# programador_ATtiny_easyeda.net
KiCad netlist of a schematic drawn in EasyEDA
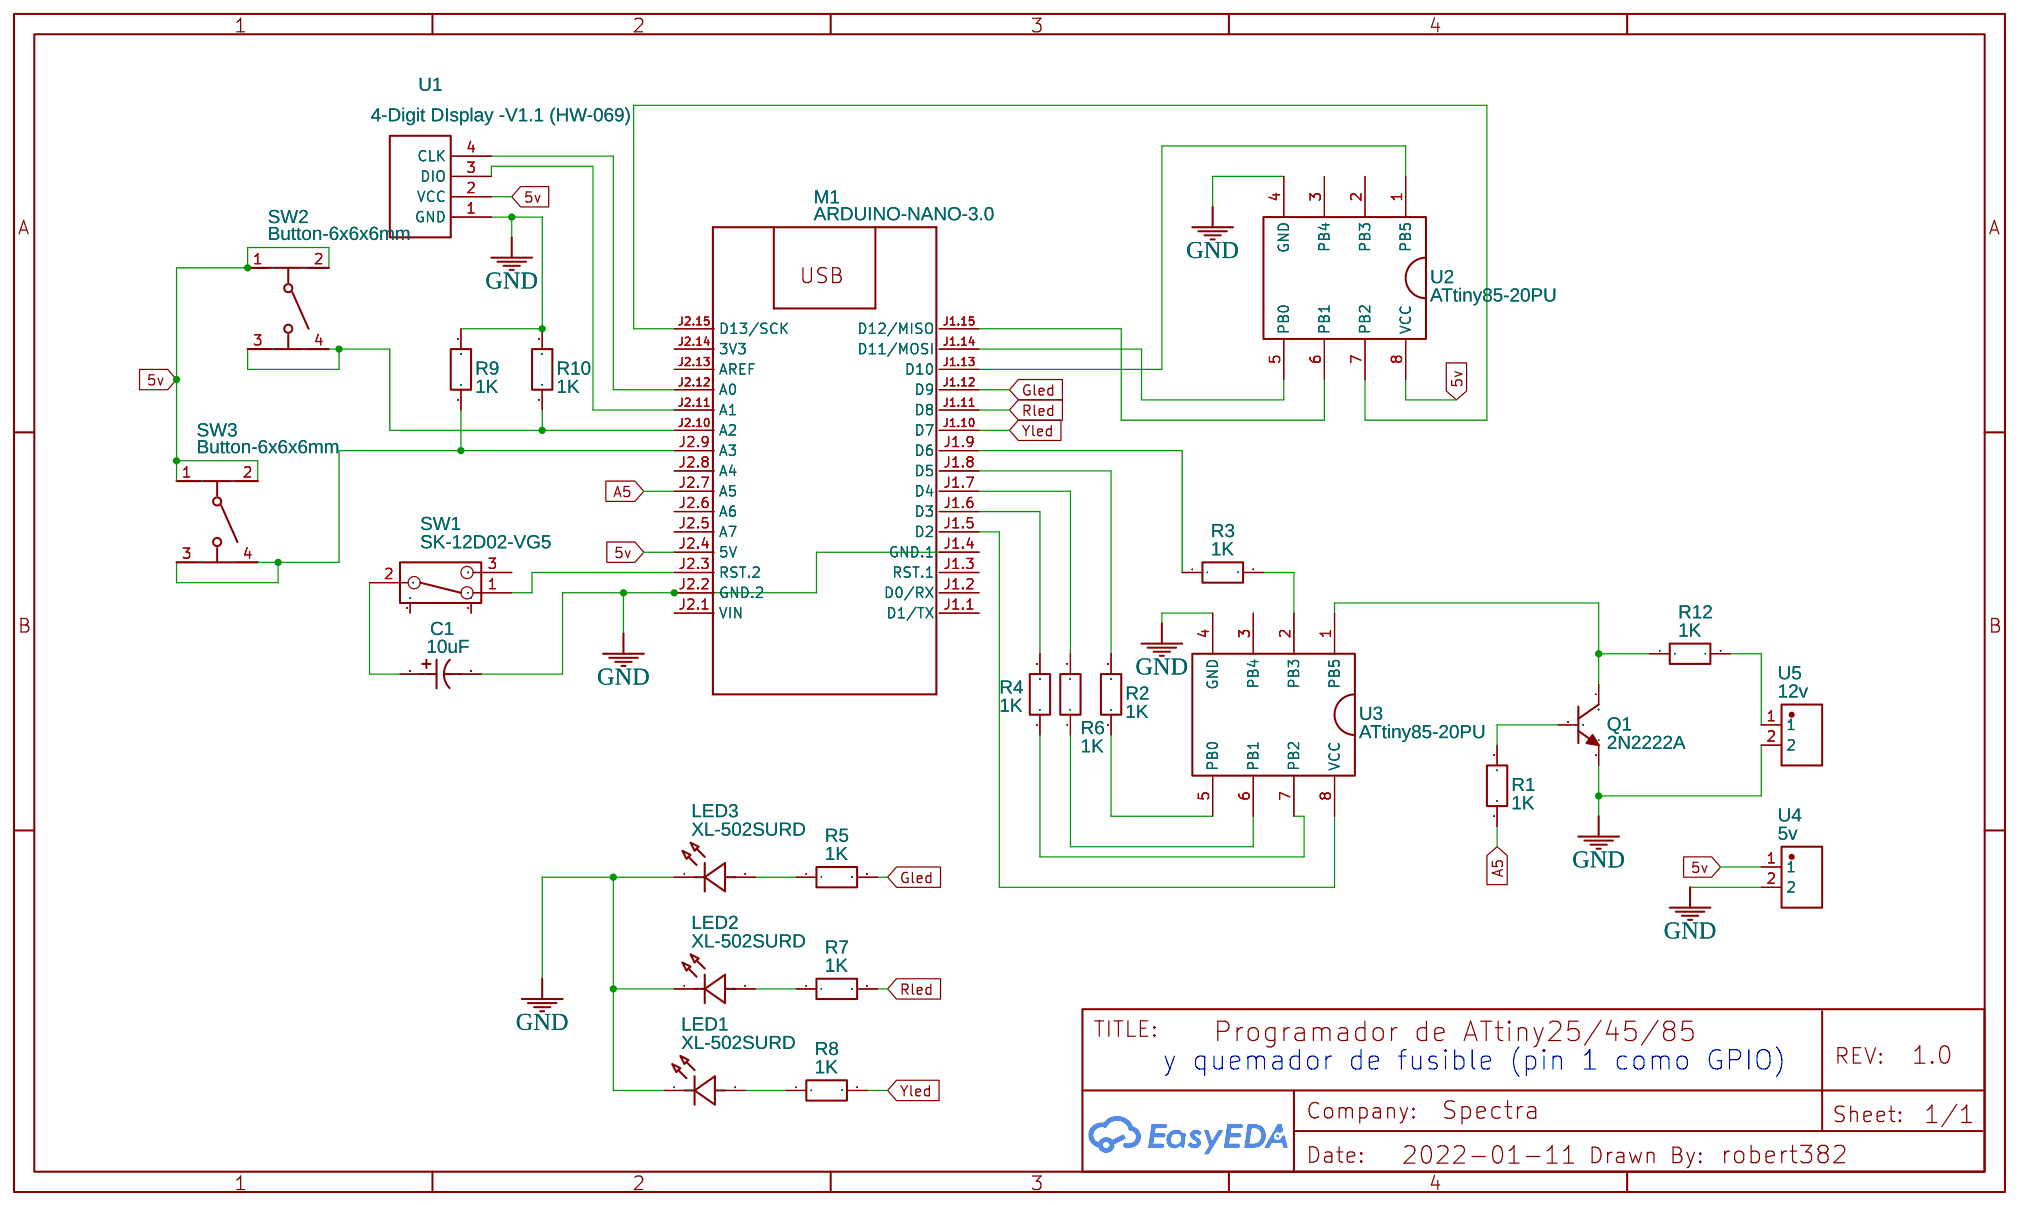
[diagram p0: schematic sheet]

(export (version "E")
  (design (tool "Eeschema 10.0.6"))
  (components
    (comp (ref "C1")
      (value "10uF")
      (fields
        (field (name "BOM_Manufacturer Part") "RA3-50V100ME3#")
        (field (name "BOM_Supplier Part") "C399591")
      )
      (libsource (lib "") (part "RA3-50V100ME3#"))
    )
    (comp (ref "LED1")
      (value "XL-502SURD")
      (fields (field (name "BOM_Supplier Part") "C2895492"))
      (libsource (lib "") (part "XL-502SURD"))
    )
    (comp (ref "LED2")
      (value "XL-502SURD")
      (fields (field (name "BOM_Supplier Part") "C2895492"))
      (libsource (lib "") (part "XL-502SURD"))
    )
    (comp (ref "LED3")
      (value "XL-502SURD")
      (fields (field (name "BOM_Supplier Part") "C2895492"))
      (libsource (lib "") (part "XL-502SURD"))
    )
    (comp (ref "M1") (value "ARDUINO-NANO-3.0") (libsource (lib "") (part "ARDUINO-NANO-3.0")))
    (comp (ref "Q1")
      (value "2N2222A")
      (fields (field (name "BOM_Supplier Part") "C358533"))
      (libsource (lib "") (part "2N2222A"))
    )
    (comp (ref "R1")
      (value "1K")
      (fields
        (field (name "BOM_Manufacturer Part") "MFR0W8F1001A50")
        (field (name "BOM_Supplier Part") "C61238")
      )
      (libsource (lib "") (part "MFR0W8F1001A50_C61238_1"))
    )
    (comp (ref "R2")
      (value "1K")
      (fields
        (field (name "BOM_Manufacturer Part") "MFR0W8F1001A50")
        (field (name "BOM_Supplier Part") "C61238")
      )
      (libsource (lib "") (part "MFR0W8F1001A50_C61238_1"))
    )
    (comp (ref "R3")
      (value "1K")
      (fields
        (field (name "BOM_Manufacturer Part") "MFR0W8F1001A50")
        (field (name "BOM_Supplier Part") "C61238")
      )
      (libsource (lib "") (part "MFR0W8F1001A50_C61238"))
    )
    (comp (ref "R4")
      (value "1K")
      (fields
        (field (name "BOM_Manufacturer Part") "MFR0W8F1001A50")
        (field (name "BOM_Supplier Part") "C61238")
      )
      (libsource (lib "") (part "MFR0W8F1001A50_C61238_1"))
    )
    (comp (ref "R5")
      (value "1K")
      (fields
        (field (name "BOM_Manufacturer Part") "MFR0W8F1001A50")
        (field (name "BOM_Supplier Part") "C61238")
      )
      (libsource (lib "") (part "MFR0W8F1001A50_C61238"))
    )
    (comp (ref "R6")
      (value "1K")
      (fields
        (field (name "BOM_Manufacturer Part") "MFR0W8F1001A50")
        (field (name "BOM_Supplier Part") "C61238")
      )
      (libsource (lib "") (part "MFR0W8F1001A50_C61238_1"))
    )
    (comp (ref "R7")
      (value "1K")
      (fields
        (field (name "BOM_Manufacturer Part") "MFR0W8F1001A50")
        (field (name "BOM_Supplier Part") "C61238")
      )
      (libsource (lib "") (part "MFR0W8F1001A50_C61238"))
    )
    (comp (ref "R8")
      (value "1K")
      (fields
        (field (name "BOM_Manufacturer Part") "MFR0W8F1001A50")
        (field (name "BOM_Supplier Part") "C61238")
      )
      (libsource (lib "") (part "MFR0W8F1001A50_C61238"))
    )
    (comp (ref "R9")
      (value "1K")
      (fields
        (field (name "BOM_Manufacturer Part") "MFR0W8F1001A50")
        (field (name "BOM_Supplier Part") "C61238")
      )
      (libsource (lib "") (part "MFR0W8F1001A50_C61238_1"))
    )
    (comp (ref "R10")
      (value "1K")
      (fields
        (field (name "BOM_Manufacturer Part") "MFR0W8F1001A50")
        (field (name "BOM_Supplier Part") "C61238")
      )
      (libsource (lib "") (part "MFR0W8F1001A50_C61238_1"))
    )
    (comp (ref "R12")
      (value "1K")
      (fields
        (field (name "BOM_Manufacturer Part") "MFR0W8F1001A50")
        (field (name "BOM_Supplier Part") "C61238")
      )
      (libsource (lib "") (part "MFR0W8F1001A50_C61238"))
    )
    (comp (ref "SW1")
      (value "SK-12D02-VG5")
      (fields (field (name "BOM_Supplier Part") "C136722"))
      (libsource (lib "") (part "SK-12D02-VG5"))
    )
    (comp (ref "SW2")
      (value "Button-6x6x6mm")
      (fields
        (field (name "BOM_Manufacturer Part") "Switch,6*6*6Plastic head,260G, 0.25mm,Straight line")
        (field (name "BOM_Supplier Part") "C71836")
      )
      (libsource (lib "") (part "Button-6x6x6mm"))
    )
    (comp (ref "SW3")
      (value "Button-6x6x6mm")
      (fields
        (field (name "BOM_Manufacturer Part") "Switch,6*6*6Plastic head,260G, 0.25mm,Straight line")
        (field (name "BOM_Supplier Part") "C71836")
      )
      (libsource (lib "") (part "Button-6x6x6mm"))
    )
    (comp (ref "U1")
      (value "4-Digit DIsplay -V1.1 (HW-069)")
      (libsource (lib "") (part "4-Digit DIsplay -V1.1 (HW-069)"))
    )
    (comp (ref "U2")
      (value "ATtiny85-20PU")
      (fields
        (field (name "BOM_Manufacturer Part") "ATTINY85-20PU")
        (field (name "BOM_Supplier Part") "556-ATTINY85-20PU")
      )
      (libsource (lib "") (part "ATtiny85-20PU"))
    )
    (comp (ref "U3")
      (value "ATtiny85-20PU")
      (fields
        (field (name "BOM_Manufacturer Part") "ATTINY85-20PU")
        (field (name "BOM_Supplier Part") "556-ATTINY85-20PU")
      )
      (libsource (lib "") (part "ATtiny85-20PU"))
    )
    (comp (ref "U4")
      (value "5v")
      (fields
        (field (name "BOM_Manufacturer Part") "KY0200500000G")
        (field (name "BOM_Supplier Part") "C967069")
      )
      (libsource (lib "") (part "KY0200500000G"))
    )
    (comp (ref "U5")
      (value "12v")
      (fields
        (field (name "BOM_Manufacturer Part") "KY0200500000G")
        (field (name "BOM_Supplier Part") "C967069")
      )
      (libsource (lib "") (part "KY0200500000G"))
    )
  )
  (nets
    (net (code "1") (name "5v") (class "Default")
      (node (ref "M1") (pin "J2.4") (pinfunction "5V_J2.4") (pintype "bidirectional"))
      (node (ref "SW2") (pin "1") (pinfunction "1_1") (pintype "unspecified"))
      (node (ref "SW2") (pin "2") (pinfunction "2_2") (pintype "unspecified"))
      (node (ref "SW3") (pin "1") (pinfunction "1_1") (pintype "unspecified"))
      (node (ref "SW3") (pin "2") (pinfunction "2_2") (pintype "unspecified"))
      (node (ref "U1") (pin "2") (pinfunction "VCC_2") (pintype "unspecified"))
      (node (ref "U2") (pin "8") (pinfunction "VCC_8") (pintype "unspecified"))
      (node (ref "U4") (pin "1") (pinfunction "1_1") (pintype "unspecified"))
    )
    (net (code "2") (name "A5") (class "Default")
      (node (ref "M1") (pin "J2.7") (pinfunction "A5_J2.7") (pintype "bidirectional"))
      (node (ref "R1") (pin "1") (pinfunction "1_1") (pintype "unspecified"))
    )
    (net (code "3") (name "GND") (class "Default")
      (node (ref "C1") (pin "2") (pinfunction "2_2") (pintype "input"))
      (node (ref "LED1") (pin "1") (pinfunction "K_1") (pintype "unspecified"))
      (node (ref "LED2") (pin "1") (pinfunction "K_1") (pintype "unspecified"))
      (node (ref "LED3") (pin "1") (pinfunction "K_1") (pintype "unspecified"))
      (node (ref "M1") (pin "J1.4") (pinfunction "GND.1_J1.4") (pintype "bidirectional"))
      (node (ref "M1") (pin "J2.2") (pinfunction "GND.2_J2.2") (pintype "bidirectional"))
      (node (ref "Q1") (pin "3") (pinfunction "E_3") (pintype "unspecified"))
      (node (ref "R10") (pin "2") (pinfunction "2_2") (pintype "unspecified"))
      (node (ref "R9") (pin "2") (pinfunction "2_2") (pintype "unspecified"))
      (node (ref "U1") (pin "1") (pinfunction "GND_1") (pintype "unspecified"))
      (node (ref "U2") (pin "4") (pinfunction "GND_4") (pintype "unspecified"))
      (node (ref "U3") (pin "4") (pinfunction "GND_4") (pintype "unspecified"))
      (node (ref "U4") (pin "2") (pinfunction "2_2") (pintype "unspecified"))
      (node (ref "U5") (pin "2") (pinfunction "2_2") (pintype "unspecified"))
    )
    (net (code "4") (name "Gled") (class "Default")
      (node (ref "M1") (pin "J1.12") (pinfunction "D9_J1.12") (pintype "bidirectional"))
      (node (ref "R5") (pin "2") (pinfunction "2_2") (pintype "unspecified"))
    )
    (net (code "5") (name "Net-(C1-Pad1)") (class "Default")
      (node (ref "C1") (pin "1") (pinfunction "1_1") (pintype "input"))
      (node (ref "SW1") (pin "2") (pinfunction "2_2") (pintype "unspecified"))
    )
    (net (code "6") (name "Net-(LED1-A)") (class "Default")
      (node (ref "LED1") (pin "2") (pinfunction "A_2") (pintype "unspecified"))
      (node (ref "R8") (pin "1") (pinfunction "1_1") (pintype "unspecified"))
    )
    (net (code "7") (name "Net-(LED2-A)") (class "Default")
      (node (ref "LED2") (pin "2") (pinfunction "A_2") (pintype "unspecified"))
      (node (ref "R7") (pin "1") (pinfunction "1_1") (pintype "unspecified"))
    )
    (net (code "8") (name "Net-(LED3-A)") (class "Default")
      (node (ref "LED3") (pin "2") (pinfunction "A_2") (pintype "unspecified"))
      (node (ref "R5") (pin "1") (pinfunction "1_1") (pintype "unspecified"))
    )
    (net (code "9") (name "Net-(M1-A0)") (class "Default")
      (node (ref "M1") (pin "J2.12") (pinfunction "A0_J2.12") (pintype "bidirectional"))
      (node (ref "U1") (pin "4") (pinfunction "CLK_4") (pintype "unspecified"))
    )
    (net (code "10") (name "Net-(M1-A1)") (class "Default")
      (node (ref "M1") (pin "J2.11") (pinfunction "A1_J2.11") (pintype "bidirectional"))
      (node (ref "U1") (pin "3") (pinfunction "DIO_3") (pintype "unspecified"))
    )
    (net (code "11") (name "Net-(M1-A2)") (class "Default")
      (node (ref "M1") (pin "J2.10") (pinfunction "A2_J2.10") (pintype "bidirectional"))
      (node (ref "R10") (pin "1") (pinfunction "1_1") (pintype "unspecified"))
      (node (ref "SW2") (pin "3") (pinfunction "3_3") (pintype "unspecified"))
      (node (ref "SW2") (pin "4") (pinfunction "4_4") (pintype "unspecified"))
    )
    (net (code "12") (name "Net-(M1-A3)") (class "Default")
      (node (ref "M1") (pin "J2.9") (pinfunction "A3_J2.9") (pintype "bidirectional"))
      (node (ref "R9") (pin "1") (pinfunction "1_1") (pintype "unspecified"))
      (node (ref "SW3") (pin "3") (pinfunction "3_3") (pintype "unspecified"))
      (node (ref "SW3") (pin "4") (pinfunction "4_4") (pintype "unspecified"))
    )
    (net (code "13") (name "Net-(M1-D2)") (class "Default")
      (node (ref "M1") (pin "J1.5") (pinfunction "D2_J1.5") (pintype "bidirectional"))
      (node (ref "U3") (pin "8") (pinfunction "VCC_8") (pintype "unspecified"))
    )
    (net (code "14") (name "Net-(M1-D3)") (class "Default")
      (node (ref "M1") (pin "J1.6") (pinfunction "D3_J1.6") (pintype "bidirectional"))
      (node (ref "R4") (pin "2") (pinfunction "2_2") (pintype "unspecified"))
    )
    (net (code "15") (name "Net-(M1-D4)") (class "Default")
      (node (ref "M1") (pin "J1.7") (pinfunction "D4_J1.7") (pintype "bidirectional"))
      (node (ref "R6") (pin "2") (pinfunction "2_2") (pintype "unspecified"))
    )
    (net (code "16") (name "Net-(M1-D5)") (class "Default")
      (node (ref "M1") (pin "J1.8") (pinfunction "D5_J1.8") (pintype "bidirectional"))
      (node (ref "R2") (pin "2") (pinfunction "2_2") (pintype "unspecified"))
    )
    (net (code "17") (name "Net-(M1-D6)") (class "Default")
      (node (ref "M1") (pin "J1.9") (pinfunction "D6_J1.9") (pintype "bidirectional"))
      (node (ref "R3") (pin "1") (pinfunction "1_1") (pintype "unspecified"))
    )
    (net (code "18") (name "Net-(M1-D10)") (class "Default")
      (node (ref "M1") (pin "J1.13") (pinfunction "D10_J1.13") (pintype "bidirectional"))
      (node (ref "U2") (pin "1") (pinfunction "PB5_1") (pintype "unspecified"))
    )
    (net (code "19") (name "Net-(M1-D11{slash}MOSI)") (class "Default")
      (node (ref "M1") (pin "J1.14") (pinfunction "D11/MOSI_J1.14") (pintype "bidirectional"))
      (node (ref "U2") (pin "5") (pinfunction "PB0_5") (pintype "unspecified"))
    )
    (net (code "20") (name "Net-(M1-D12{slash}MISO)") (class "Default")
      (node (ref "M1") (pin "J1.15") (pinfunction "D12/MISO_J1.15") (pintype "bidirectional"))
      (node (ref "U2") (pin "6") (pinfunction "PB1_6") (pintype "unspecified"))
    )
    (net (code "21") (name "Net-(M1-D13{slash}SCK)") (class "Default")
      (node (ref "M1") (pin "J2.15") (pinfunction "D13/SCK_J2.15") (pintype "bidirectional"))
      (node (ref "U2") (pin "7") (pinfunction "PB2_7") (pintype "unspecified"))
    )
    (net (code "22") (name "Net-(M1-RST.2)") (class "Default")
      (node (ref "M1") (pin "J2.3") (pinfunction "RST.2_J2.3") (pintype "bidirectional"))
      (node (ref "SW1") (pin "1") (pinfunction "1_1") (pintype "unspecified"))
    )
    (net (code "23") (name "Net-(Q1-B)") (class "Default")
      (node (ref "Q1") (pin "2") (pinfunction "B_2") (pintype "unspecified"))
      (node (ref "R1") (pin "2") (pinfunction "2_2") (pintype "unspecified"))
    )
    (net (code "24") (name "Net-(Q1-C)") (class "Default")
      (node (ref "Q1") (pin "1") (pinfunction "C_1") (pintype "unspecified"))
      (node (ref "R12") (pin "1") (pinfunction "1_1") (pintype "unspecified"))
      (node (ref "U3") (pin "1") (pinfunction "PB5_1") (pintype "unspecified"))
    )
    (net (code "25") (name "Net-(R12-Pad2)") (class "Default")
      (node (ref "R12") (pin "2") (pinfunction "2_2") (pintype "unspecified"))
      (node (ref "U5") (pin "1") (pinfunction "1_1") (pintype "unspecified"))
    )
    (net (code "26") (name "Net-(U3-PB0)") (class "Default")
      (node (ref "R2") (pin "1") (pinfunction "1_1") (pintype "unspecified"))
      (node (ref "U3") (pin "5") (pinfunction "PB0_5") (pintype "unspecified"))
    )
    (net (code "27") (name "Net-(U3-PB1)") (class "Default")
      (node (ref "R6") (pin "1") (pinfunction "1_1") (pintype "unspecified"))
      (node (ref "U3") (pin "6") (pinfunction "PB1_6") (pintype "unspecified"))
    )
    (net (code "28") (name "Net-(U3-PB2)") (class "Default")
      (node (ref "R4") (pin "1") (pinfunction "1_1") (pintype "unspecified"))
      (node (ref "U3") (pin "7") (pinfunction "PB2_7") (pintype "unspecified"))
    )
    (net (code "29") (name "Net-(U3-PB3)") (class "Default")
      (node (ref "R3") (pin "2") (pinfunction "2_2") (pintype "unspecified"))
      (node (ref "U3") (pin "2") (pinfunction "PB3_2") (pintype "unspecified"))
    )
    (net (code "30") (name "Rled") (class "Default")
      (node (ref "M1") (pin "J1.11") (pinfunction "D8_J1.11") (pintype "bidirectional"))
      (node (ref "R7") (pin "2") (pinfunction "2_2") (pintype "unspecified"))
    )
    (net (code "31") (name "Yled") (class "Default")
      (node (ref "M1") (pin "J1.10") (pinfunction "D7_J1.10") (pintype "bidirectional"))
      (node (ref "R8") (pin "2") (pinfunction "2_2") (pintype "unspecified"))
    )
    (net (code "32") (name "unconnected-(M1-3V3-PadJ2.14)") (class "Default")
      (node (ref "M1") (pin "J2.14") (pinfunction "3V3_J2.14") (pintype "bidirectional"))
    )
    (net (code "33") (name "unconnected-(M1-A4-PadJ2.8)") (class "Default")
      (node (ref "M1") (pin "J2.8") (pinfunction "A4_J2.8") (pintype "bidirectional"))
    )
    (net (code "34") (name "unconnected-(M1-A6-PadJ2.6)") (class "Default")
      (node (ref "M1") (pin "J2.6") (pinfunction "A6_J2.6") (pintype "bidirectional"))
    )
    (net (code "35") (name "unconnected-(M1-A7-PadJ2.5)") (class "Default")
      (node (ref "M1") (pin "J2.5") (pinfunction "A7_J2.5") (pintype "bidirectional"))
    )
    (net (code "36") (name "unconnected-(M1-AREF-PadJ2.13)") (class "Default")
      (node (ref "M1") (pin "J2.13") (pinfunction "AREF_J2.13") (pintype "bidirectional"))
    )
    (net (code "37") (name "unconnected-(M1-D0{slash}RX-PadJ1.2)") (class "Default")
      (node (ref "M1") (pin "J1.2") (pinfunction "D0/RX_J1.2") (pintype "bidirectional"))
    )
    (net (code "38") (name "unconnected-(M1-D1{slash}TX-PadJ1.1)") (class "Default")
      (node (ref "M1") (pin "J1.1") (pinfunction "D1/TX_J1.1") (pintype "bidirectional"))
    )
    (net (code "39") (name "unconnected-(M1-RST.1-PadJ1.3)") (class "Default")
      (node (ref "M1") (pin "J1.3") (pinfunction "RST.1_J1.3") (pintype "bidirectional"))
    )
    (net (code "40") (name "unconnected-(M1-VIN-PadJ2.1)") (class "Default")
      (node (ref "M1") (pin "J2.1") (pinfunction "VIN_J2.1") (pintype "bidirectional"))
    )
    (net (code "41") (name "unconnected-(SW1-Pad3)") (class "Default")
      (node (ref "SW1") (pin "3") (pinfunction "3_3") (pintype "unspecified"))
    )
    (net (code "42") (name "unconnected-(SW1-Pad4)") (class "Default")
      (node (ref "SW1") (pin "4") (pinfunction "4_4") (pintype "unspecified"))
    )
    (net (code "43") (name "unconnected-(SW1-Pad5)") (class "Default")
      (node (ref "SW1") (pin "5") (pinfunction "5_5") (pintype "unspecified"))
    )
    (net (code "44") (name "unconnected-(U2-PB3-Pad2)") (class "Default")
      (node (ref "U2") (pin "2") (pinfunction "PB3_2") (pintype "unspecified"))
    )
    (net (code "45") (name "unconnected-(U2-PB4-Pad3)") (class "Default")
      (node (ref "U2") (pin "3") (pinfunction "PB4_3") (pintype "unspecified"))
    )
    (net (code "46") (name "unconnected-(U3-PB4-Pad3)") (class "Default")
      (node (ref "U3") (pin "3") (pinfunction "PB4_3") (pintype "unspecified"))
    )
  )
)
